# ESP_LoRa_Scale_V1_60.net
KiCad netlist of a schematic drawn in EAGLE
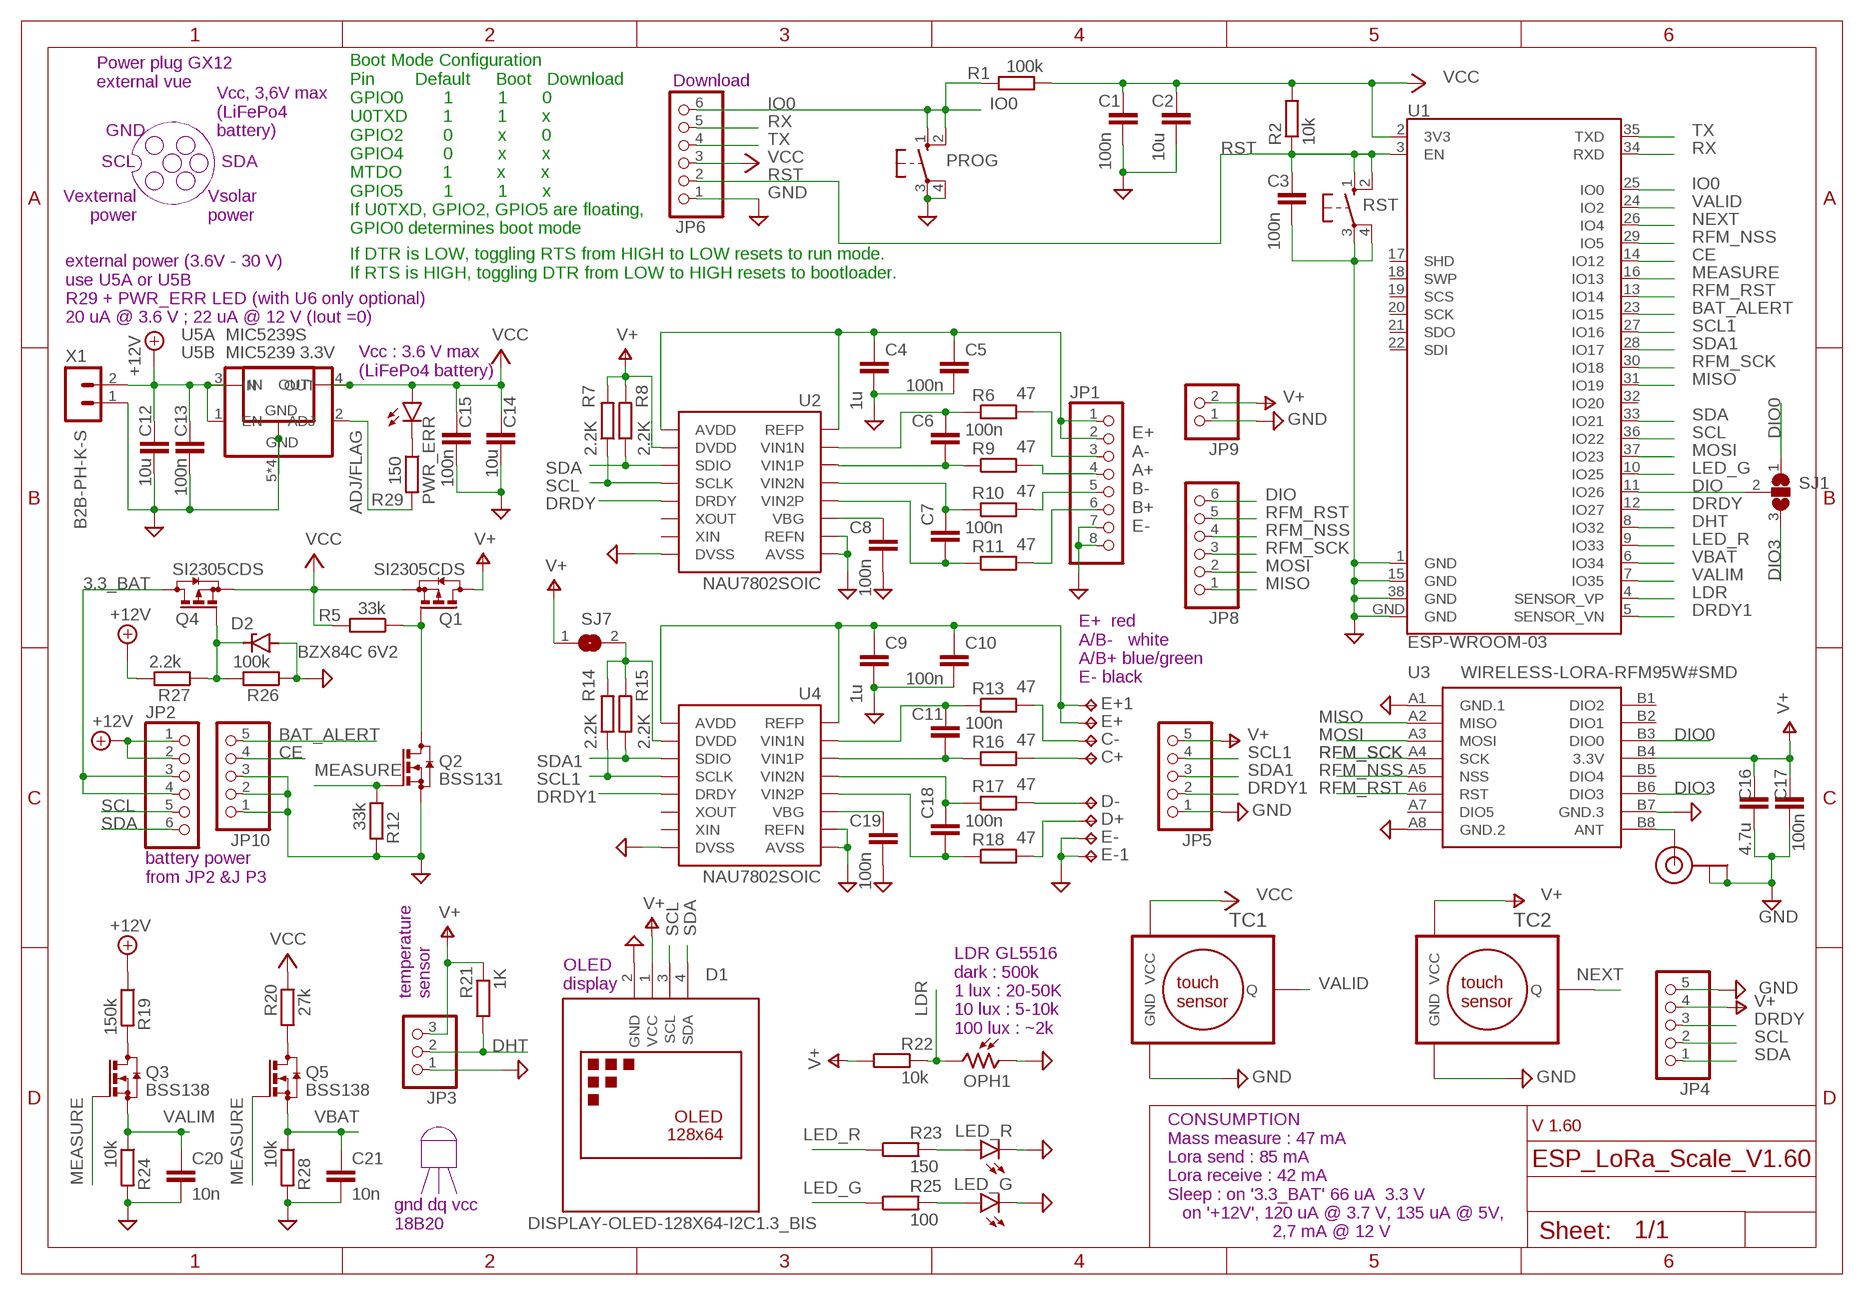
[diagram p0: schematic, sheet 1]

(export (version "E")
  (design (tool "Eeschema 10.0.6"))
  (components
    (comp (ref "C+")
      (value "TPTP17SQ")
      (footprint "eagle-import:TP17SQ")
      (libsource (lib "eagle-import") (part "TPTP17SQ"))
    )
    (comp (ref "C-")
      (value "TPTP17SQ")
      (footprint "eagle-import:TP17SQ")
      (libsource (lib "eagle-import") (part "TPTP17SQ"))
    )
    (comp (ref "C1")
      (value "100n")
      (footprint "eagle-import:C1206")
      (libsource (lib "eagle-import") (part "CC1206"))
    )
    (comp (ref "C2")
      (value "10u")
      (footprint "eagle-import:C1210")
      (libsource (lib "eagle-import") (part "CC1210"))
    )
    (comp (ref "C3")
      (value "100n")
      (footprint "eagle-import:C1206")
      (libsource (lib "eagle-import") (part "CC1206"))
    )
    (comp (ref "C4")
      (value "1u")
      (footprint "eagle-import:C1210")
      (libsource (lib "eagle-import") (part "CC1210"))
    )
    (comp (ref "C5")
      (value "100n")
      (footprint "eagle-import:C1206")
      (libsource (lib "eagle-import") (part "CC1206"))
    )
    (comp (ref "C6")
      (value "100n")
      (footprint "eagle-import:C1206")
      (libsource (lib "eagle-import") (part "CC1206"))
    )
    (comp (ref "C7")
      (value "100n")
      (footprint "eagle-import:C1206")
      (libsource (lib "eagle-import") (part "CC1206"))
    )
    (comp (ref "C8")
      (value "100n")
      (footprint "eagle-import:C1206")
      (libsource (lib "eagle-import") (part "CC1206"))
    )
    (comp (ref "C9")
      (value "1u")
      (footprint "eagle-import:C1210")
      (libsource (lib "eagle-import") (part "CC1210"))
    )
    (comp (ref "C10")
      (value "100n")
      (footprint "eagle-import:C1206")
      (libsource (lib "eagle-import") (part "CC1206"))
    )
    (comp (ref "C11")
      (value "100n")
      (footprint "eagle-import:C1206")
      (libsource (lib "eagle-import") (part "CC1206"))
    )
    (comp (ref "C12")
      (value "10u")
      (footprint "eagle-import:C1210")
      (libsource (lib "eagle-import") (part "CC1210"))
    )
    (comp (ref "C13")
      (value "100n")
      (footprint "eagle-import:C1206")
      (libsource (lib "eagle-import") (part "CC1206"))
    )
    (comp (ref "C14")
      (value "10u")
      (footprint "eagle-import:C1210")
      (libsource (lib "eagle-import") (part "CC1210"))
    )
    (comp (ref "C15")
      (value "100n")
      (footprint "eagle-import:C1206")
      (libsource (lib "eagle-import") (part "CC1206"))
    )
    (comp (ref "C16")
      (value "4.7u")
      (footprint "eagle-import:C1210")
      (libsource (lib "eagle-import") (part "CC1210"))
    )
    (comp (ref "C17")
      (value "100n")
      (footprint "eagle-import:C1206")
      (libsource (lib "eagle-import") (part "CC1206"))
    )
    (comp (ref "C18")
      (value "100n")
      (footprint "eagle-import:C1206")
      (libsource (lib "eagle-import") (part "CC1206"))
    )
    (comp (ref "C19")
      (value "100n")
      (footprint "eagle-import:C1206")
      (libsource (lib "eagle-import") (part "CC1206"))
    )
    (comp (ref "C20")
      (value "10n")
      (footprint "eagle-import:C1206")
      (libsource (lib "eagle-import") (part "CC1206"))
    )
    (comp (ref "C21")
      (value "10n")
      (footprint "eagle-import:C1206")
      (libsource (lib "eagle-import") (part "CC1206"))
    )
    (comp (ref "D+")
      (value "TPTP17SQ")
      (footprint "eagle-import:TP17SQ")
      (libsource (lib "eagle-import") (part "TPTP17SQ"))
    )
    (comp (ref "D-")
      (value "TPTP17SQ")
      (footprint "eagle-import:TP17SQ")
      (libsource (lib "eagle-import") (part "TPTP17SQ"))
    )
    (comp (ref "D1")
      (value "DISPLAY-OLED-128X64-I2C1.3_BIS")
      (footprint "eagle-import:DISPLAY-OLED-128X64-1.3-I2C_BIS")
      (libsource (lib "eagle-import") (part "DISPLAY-OLED-128X64-I2C1.3_BIS"))
    )
    (comp (ref "D2")
      (value "BZX84C 6V2")
      (footprint "eagle-import:TO236")
      (libsource (lib "eagle-import") (part "BZX84CSMD"))
    )
    (comp (ref "E+")
      (value "TPTP17SQ")
      (footprint "eagle-import:TP17SQ")
      (libsource (lib "eagle-import") (part "TPTP17SQ"))
    )
    (comp (ref "E+1")
      (value "TPTP17SQ")
      (footprint "eagle-import:TP17SQ")
      (libsource (lib "eagle-import") (part "TPTP17SQ"))
    )
    (comp (ref "E-")
      (value "TPTP17SQ")
      (footprint "eagle-import:TP17SQ")
      (libsource (lib "eagle-import") (part "TPTP17SQ"))
    )
    (comp (ref "E-1")
      (value "TPTP17SQ")
      (footprint "eagle-import:TP17SQ")
      (libsource (lib "eagle-import") (part "TPTP17SQ"))
    )
    (comp (ref "J1")
      (value "U.FL")
      (footprint "eagle-import:U.FL")
      (libsource (lib "eagle-import") (part "U.FL"))
    )
    (comp (ref "JP1")
      (value "PINHD-1X8")
      (footprint "eagle-import:1X08")
      (libsource (lib "eagle-import") (part "PINHD-1X8"))
    )
    (comp (ref "JP2")
      (value "PINHD-1X6")
      (footprint "eagle-import:1X06")
      (libsource (lib "eagle-import") (part "PINHD-1X6"))
    )
    (comp (ref "JP3")
      (value "PINHD-1X3")
      (footprint "eagle-import:1X03")
      (libsource (lib "eagle-import") (part "PINHD-1X3"))
    )
    (comp (ref "JP4")
      (value "PINHD-1X5")
      (footprint "eagle-import:1X05")
      (libsource (lib "eagle-import") (part "PINHD-1X5"))
    )
    (comp (ref "JP5")
      (value "PINHD-1X5")
      (footprint "eagle-import:1X05")
      (libsource (lib "eagle-import") (part "PINHD-1X5"))
    )
    (comp (ref "JP6")
      (value "PINHD-1X6")
      (footprint "eagle-import:1X06")
      (libsource (lib "eagle-import") (part "PINHD-1X6"))
    )
    (comp (ref "JP8")
      (value "PINHD-1X6")
      (footprint "eagle-import:1X06")
      (libsource (lib "eagle-import") (part "PINHD-1X6"))
    )
    (comp (ref "JP9")
      (value "PINHD-1X2")
      (footprint "eagle-import:1X02")
      (libsource (lib "eagle-import") (part "PINHD-1X2"))
    )
    (comp (ref "JP10")
      (value "PINHD-1X5")
      (footprint "eagle-import:1X05")
      (libsource (lib "eagle-import") (part "PINHD-1X5"))
    )
    (comp (ref "LED_G")
      (value "LEDSMT1206")
      (footprint "eagle-import:1206")
      (libsource (lib "eagle-import") (part "LEDSMT1206"))
    )
    (comp (ref "LED_R")
      (value "LEDSMT1206")
      (footprint "eagle-import:1206")
      (libsource (lib "eagle-import") (part "LEDSMT1206"))
    )
    (comp (ref "OPH1")
      (value "VT93N2")
      (footprint "eagle-import:VT900")
      (libsource (lib "eagle-import") (part "VT93N2"))
    )
    (comp (ref "PROG")
      (value "10-XX")
      (footprint "eagle-import:B3F-10XX")
      (fields (field (name "MPN") "B3F-1000"))
      (libsource (lib "eagle-import") (part "10-XX"))
    )
    (comp (ref "PWR_ERR")
      (value "LEDSMT1206")
      (footprint "eagle-import:1206")
      (libsource (lib "eagle-import") (part "LEDSMT1206"))
    )
    (comp (ref "Q1")
      (value "SI2305CDS")
      (footprint "eagle-import:SOT23")
      (libsource (lib "eagle-import") (part "SI2305CDS"))
    )
    (comp (ref "Q2")
      (value "BSS131")
      (footprint "eagle-import:SOT23")
      (libsource (lib "eagle-import") (part "BSS131"))
    )
    (comp (ref "Q3")
      (value "BSS138")
      (footprint "eagle-import:SOT23")
      (libsource (lib "eagle-import") (part "BSS138"))
    )
    (comp (ref "Q4")
      (value "SI2305CDS")
      (footprint "eagle-import:SOT23")
      (libsource (lib "eagle-import") (part "SI2305CDS"))
    )
    (comp (ref "Q5")
      (value "BSS138")
      (footprint "eagle-import:SOT23")
      (libsource (lib "eagle-import") (part "BSS138"))
    )
    (comp (ref "R1")
      (value "100k")
      (footprint "eagle-import:R1206")
      (libsource (lib "eagle-import") (part "RR1206"))
    )
    (comp (ref "R2")
      (value "10k")
      (footprint "eagle-import:R1206")
      (libsource (lib "eagle-import") (part "RR1206"))
    )
    (comp (ref "R5")
      (value "33k")
      (footprint "eagle-import:R1206")
      (libsource (lib "eagle-import") (part "RR1206"))
    )
    (comp (ref "R6")
      (value "47")
      (footprint "eagle-import:R1206")
      (libsource (lib "eagle-import") (part "RR1206"))
    )
    (comp (ref "R7")
      (value "2.2K")
      (footprint "eagle-import:R1206")
      (libsource (lib "eagle-import") (part "RR1206"))
    )
    (comp (ref "R8")
      (value "2.2K")
      (footprint "eagle-import:R1206")
      (libsource (lib "eagle-import") (part "RR1206"))
    )
    (comp (ref "R9")
      (value "47")
      (footprint "eagle-import:R1206")
      (libsource (lib "eagle-import") (part "RR1206"))
    )
    (comp (ref "R10")
      (value "47")
      (footprint "eagle-import:R1206")
      (libsource (lib "eagle-import") (part "RR1206"))
    )
    (comp (ref "R11")
      (value "47")
      (footprint "eagle-import:R1206")
      (libsource (lib "eagle-import") (part "RR1206"))
    )
    (comp (ref "R12")
      (value "33k")
      (footprint "eagle-import:R1206")
      (libsource (lib "eagle-import") (part "RR1206"))
    )
    (comp (ref "R13")
      (value "47")
      (footprint "eagle-import:R1206")
      (libsource (lib "eagle-import") (part "RR1206"))
    )
    (comp (ref "R14")
      (value "2.2K")
      (footprint "eagle-import:R1206")
      (libsource (lib "eagle-import") (part "RR1206"))
    )
    (comp (ref "R15")
      (value "2.2K")
      (footprint "eagle-import:R1206")
      (libsource (lib "eagle-import") (part "RR1206"))
    )
    (comp (ref "R16")
      (value "47")
      (footprint "eagle-import:R1206")
      (libsource (lib "eagle-import") (part "RR1206"))
    )
    (comp (ref "R17")
      (value "47")
      (footprint "eagle-import:R1206")
      (libsource (lib "eagle-import") (part "RR1206"))
    )
    (comp (ref "R18")
      (value "47")
      (footprint "eagle-import:R1206")
      (libsource (lib "eagle-import") (part "RR1206"))
    )
    (comp (ref "R19")
      (value "150k")
      (footprint "eagle-import:R1206")
      (libsource (lib "eagle-import") (part "RR1206"))
    )
    (comp (ref "R20")
      (value "27k")
      (footprint "eagle-import:R1206")
      (libsource (lib "eagle-import") (part "RR1206"))
    )
    (comp (ref "R21")
      (value "1K")
      (footprint "eagle-import:R1206")
      (libsource (lib "eagle-import") (part "RR1206"))
    )
    (comp (ref "R22")
      (value "10k")
      (footprint "eagle-import:R1206")
      (libsource (lib "eagle-import") (part "RR1206"))
    )
    (comp (ref "R23")
      (value "150")
      (footprint "eagle-import:R1206")
      (libsource (lib "eagle-import") (part "RR1206"))
    )
    (comp (ref "R24")
      (value "10k")
      (footprint "eagle-import:R1206")
      (libsource (lib "eagle-import") (part "RR1206"))
    )
    (comp (ref "R25")
      (value "100")
      (footprint "eagle-import:R1206")
      (libsource (lib "eagle-import") (part "RR1206"))
    )
    (comp (ref "R26")
      (value "100k")
      (footprint "eagle-import:R1206")
      (libsource (lib "eagle-import") (part "RR1206"))
    )
    (comp (ref "R27")
      (value "2.2k")
      (footprint "eagle-import:R1206")
      (libsource (lib "eagle-import") (part "RR1206"))
    )
    (comp (ref "R28")
      (value "10k")
      (footprint "eagle-import:R1206")
      (libsource (lib "eagle-import") (part "RR1206"))
    )
    (comp (ref "R29")
      (value "150")
      (footprint "eagle-import:R1206")
      (libsource (lib "eagle-import") (part "RR1206"))
    )
    (comp (ref "RST")
      (value "10-XX")
      (footprint "eagle-import:B3F-10XX")
      (fields (field (name "MPN") "B3F-1000"))
      (libsource (lib "eagle-import") (part "10-XX"))
    )
    (comp (ref "SJ1")
      (value "SJ2W")
      (footprint "eagle-import:SJ_2")
      (libsource (lib "eagle-import") (part "SJ2W"))
    )
    (comp (ref "SJ7") (value "SJ") (footprint "eagle-import:SJ") (libsource (lib "eagle-import") (part "SJ")))
    (comp (ref "TC1")
      (value "TTP223R_H")
      (footprint "eagle-import:TTP233RED_H")
      (libsource (lib "eagle-import") (part "TTP223R_H"))
    )
    (comp (ref "TC2")
      (value "TTP223R_H")
      (footprint "eagle-import:TTP233RED_H")
      (libsource (lib "eagle-import") (part "TTP223R_H"))
    )
    (comp (ref "U1")
      (value "ESP-WROOM-03")
      (footprint "eagle-import:ESP-WROOM-03")
      (libsource (lib "eagle-import") (part "ESP-WROOM-03"))
    )
    (comp (ref "U2")
      (value "NAU7802SOIC")
      (footprint "eagle-import:SO16")
      (libsource (lib "eagle-import") (part "NAU7802SOIC"))
    )
    (comp (ref "U3")
      (value "WIRELESS-LORA-RFM95W#SMD")
      (footprint "eagle-import:WIRELESS-LORA-RFM95W#SMD")
      (libsource (lib "eagle-import") (part "WIRELESS-LORA-RFM95W#SMD"))
    )
    (comp (ref "U4")
      (value "NAU7802SOIC")
      (footprint "eagle-import:SO16")
      (libsource (lib "eagle-import") (part "NAU7802SOIC"))
    )
    (comp (ref "U5A")
      (value "MIC5239 3.3V")
      (footprint "eagle-import:MSOP08")
      (libsource (lib "eagle-import") (part "MIC5239-ADJMM"))
    )
    (comp (ref "U5B")
      (value "MIC5239S")
      (footprint "eagle-import:SOT223")
      (libsource (lib "eagle-import") (part "MIC5239S"))
    )
    (comp (ref "X1")
      (value "B2B-PH-K-S")
      (footprint "eagle-import:B2B-PH-K-S")
      (libsource (lib "eagle-import") (part "B2B-PH-K-S"))
    )
  )
  (nets
    (net (code "1") (name "+12V") (class "Default")
      (node (ref "C12") (pin "1") (pinfunction "1_1") (pintype "passive"))
      (node (ref "C13") (pin "1") (pinfunction "1_1") (pintype "passive"))
      (node (ref "JP2") (pin "1") (pinfunction "1_1") (pintype "passive"))
      (node (ref "JP2") (pin "2") (pinfunction "2_2") (pintype "passive"))
      (node (ref "R19") (pin "1") (pinfunction "1_1") (pintype "passive"))
      (node (ref "R27") (pin "2") (pinfunction "2_2") (pintype "passive"))
      (node (ref "U5A") (pin "1") (pinfunction "EN_1") (pintype "input"))
      (node (ref "U5A") (pin "3") (pinfunction "IN_3") (pintype "input"))
      (node (ref "U5B") (pin "1") (pinfunction "IN_1") (pintype "input"))
      (node (ref "X1") (pin "2") (pinfunction "2_2") (pintype "passive"))
    )
    (net (code "2") (name "/3.3_BAT") (class "Default")
      (node (ref "JP2") (pin "3") (pinfunction "3_3") (pintype "passive"))
      (node (ref "JP2") (pin "4") (pinfunction "4_4") (pintype "passive"))
      (node (ref "Q4") (pin "3") (pinfunction "D_3") (pintype "passive"))
    )
    (net (code "3") (name "/ADJ{slash}FLAG") (class "Default")
      (node (ref "R29") (pin "2") (pinfunction "2_2") (pintype "passive"))
      (node (ref "U5A") (pin "2") (pinfunction "ADJ_2") (pintype "passive"))
    )
    (net (code "4") (name "/BAT_ALERT") (class "Default")
      (node (ref "JP10") (pin "5") (pinfunction "5_5") (pintype "passive"))
      (node (ref "U1") (pin "23") (pinfunction "IO15_23") (pintype "bidirectional"))
    )
    (net (code "5") (name "/CE") (class "Default")
      (node (ref "JP10") (pin "4") (pinfunction "4_4") (pintype "passive"))
      (node (ref "U1") (pin "14") (pinfunction "IO12_14") (pintype "bidirectional"))
    )
    (net (code "6") (name "/DHT") (class "Default")
      (node (ref "JP3") (pin "2") (pinfunction "2_2") (pintype "passive"))
      (node (ref "R21") (pin "1") (pinfunction "1_1") (pintype "passive"))
      (node (ref "U1") (pin "8") (pinfunction "IO32_8") (pintype "bidirectional"))
    )
    (net (code "7") (name "/DIO") (class "Default")
      (node (ref "JP8") (pin "6") (pinfunction "6_6") (pintype "passive"))
      (node (ref "SJ1") (pin "2") (pinfunction "2_2") (pintype "passive"))
      (node (ref "U1") (pin "11") (pinfunction "IO26_11") (pintype "bidirectional"))
    )
    (net (code "8") (name "/DIO0") (class "Default")
      (node (ref "SJ1") (pin "1") (pinfunction "1_1") (pintype "passive"))
      (node (ref "U3") (pin "B3") (pinfunction "DIO0_B3") (pintype "bidirectional"))
    )
    (net (code "9") (name "/DIO3") (class "Default")
      (node (ref "SJ1") (pin "3") (pinfunction "3_3") (pintype "passive"))
      (node (ref "U3") (pin "B6") (pinfunction "DIO3_B6") (pintype "bidirectional"))
    )
    (net (code "10") (name "/DRDY") (class "Default")
      (node (ref "JP4") (pin "3") (pinfunction "3_3") (pintype "passive"))
      (node (ref "U1") (pin "12") (pinfunction "IO27_12") (pintype "bidirectional"))
      (node (ref "U2") (pin "12") (pinfunction "DRDY_12") (pintype "bidirectional"))
    )
    (net (code "11") (name "/DRDY1") (class "Default")
      (node (ref "JP5") (pin "2") (pinfunction "2_2") (pintype "passive"))
      (node (ref "U1") (pin "5") (pinfunction "SENSOR_VN_5") (pintype "bidirectional"))
      (node (ref "U4") (pin "12") (pinfunction "DRDY_12") (pintype "bidirectional"))
    )
    (net (code "12") (name "/IO0") (class "Default")
      (node (ref "JP6") (pin "6") (pinfunction "6_6") (pintype "passive"))
      (node (ref "PROG") (pin "1") (pinfunction "S_1") (pintype "passive"))
      (node (ref "PROG") (pin "2") (pinfunction "S1_2") (pintype "passive"))
      (node (ref "R1") (pin "2") (pinfunction "2_2") (pintype "passive"))
      (node (ref "U1") (pin "25") (pinfunction "IO0_25") (pintype "bidirectional"))
    )
    (net (code "13") (name "/LDR") (class "Default")
      (node (ref "OPH1") (pin "2") (pinfunction "2_2") (pintype "passive"))
      (node (ref "R22") (pin "2") (pinfunction "2_2") (pintype "passive"))
      (node (ref "U1") (pin "4") (pinfunction "SENSOR_VP_4") (pintype "bidirectional"))
    )
    (net (code "14") (name "/LED_G") (class "Default")
      (node (ref "R25") (pin "1") (pinfunction "1_1") (pintype "passive"))
      (node (ref "U1") (pin "10") (pinfunction "IO25_10") (pintype "bidirectional"))
    )
    (net (code "15") (name "/LED_R") (class "Default")
      (node (ref "R23") (pin "1") (pinfunction "1_1") (pintype "passive"))
      (node (ref "U1") (pin "9") (pinfunction "IO33_9") (pintype "bidirectional"))
    )
    (net (code "16") (name "/MEASURE") (class "Default")
      (node (ref "Q2") (pin "1") (pinfunction "G_1") (pintype "passive"))
      (node (ref "Q3") (pin "1") (pinfunction "G_1") (pintype "passive"))
      (node (ref "Q5") (pin "1") (pinfunction "G_1") (pintype "passive"))
      (node (ref "R12") (pin "1") (pinfunction "1_1") (pintype "passive"))
      (node (ref "U1") (pin "16") (pinfunction "IO13_16") (pintype "bidirectional"))
    )
    (net (code "17") (name "/MISO") (class "Default")
      (node (ref "JP8") (pin "1") (pinfunction "1_1") (pintype "passive"))
      (node (ref "U1") (pin "31") (pinfunction "IO19_31") (pintype "bidirectional"))
      (node (ref "U3") (pin "A2") (pinfunction "MISO_A2") (pintype "bidirectional"))
    )
    (net (code "18") (name "/MOSI") (class "Default")
      (node (ref "JP8") (pin "2") (pinfunction "2_2") (pintype "passive"))
      (node (ref "U1") (pin "37") (pinfunction "IO23_37") (pintype "bidirectional"))
      (node (ref "U3") (pin "A3") (pinfunction "MOSI_A3") (pintype "bidirectional"))
    )
    (net (code "19") (name "/NEXT") (class "Default")
      (node (ref "TC2") (pin "P$2") (pinfunction "Q_P$2") (pintype "power_in"))
      (node (ref "U1") (pin "26") (pinfunction "IO4_26") (pintype "bidirectional"))
    )
    (net (code "20") (name "/RFM_NSS") (class "Default")
      (node (ref "JP8") (pin "4") (pinfunction "4_4") (pintype "passive"))
      (node (ref "U1") (pin "29") (pinfunction "IO5_29") (pintype "bidirectional"))
      (node (ref "U3") (pin "A5") (pinfunction "NSS_A5") (pintype "bidirectional"))
    )
    (net (code "21") (name "/RFM_RST") (class "Default")
      (node (ref "JP8") (pin "5") (pinfunction "5_5") (pintype "passive"))
      (node (ref "U1") (pin "13") (pinfunction "IO14_13") (pintype "bidirectional"))
      (node (ref "U3") (pin "A6") (pinfunction "RST_A6") (pintype "bidirectional"))
    )
    (net (code "22") (name "/RFM_SCK") (class "Default")
      (node (ref "JP8") (pin "3") (pinfunction "3_3") (pintype "passive"))
      (node (ref "U1") (pin "30") (pinfunction "IO18_30") (pintype "bidirectional"))
      (node (ref "U3") (pin "A4") (pinfunction "SCK_A4") (pintype "bidirectional"))
    )
    (net (code "23") (name "/RST") (class "Default")
      (node (ref "C3") (pin "1") (pinfunction "1_1") (pintype "passive"))
      (node (ref "JP6") (pin "2") (pinfunction "2_2") (pintype "passive"))
      (node (ref "R2") (pin "1") (pinfunction "1_1") (pintype "passive"))
      (node (ref "RST") (pin "1") (pinfunction "S_1") (pintype "passive"))
      (node (ref "RST") (pin "2") (pinfunction "S1_2") (pintype "passive"))
      (node (ref "U1") (pin "3") (pinfunction "EN_3") (pintype "bidirectional"))
    )
    (net (code "24") (name "/RX") (class "Default")
      (node (ref "JP6") (pin "5") (pinfunction "5_5") (pintype "passive"))
      (node (ref "U1") (pin "34") (pinfunction "RXD_34") (pintype "bidirectional"))
    )
    (net (code "25") (name "/SCL") (class "Default")
      (node (ref "D1") (pin "3") (pinfunction "SCL_3") (pintype "bidirectional"))
      (node (ref "JP2") (pin "5") (pinfunction "5_5") (pintype "passive"))
      (node (ref "JP4") (pin "2") (pinfunction "2_2") (pintype "passive"))
      (node (ref "R7") (pin "1") (pinfunction "1_1") (pintype "passive"))
      (node (ref "U1") (pin "36") (pinfunction "IO22_36") (pintype "bidirectional"))
      (node (ref "U2") (pin "13") (pinfunction "SCLK_13") (pintype "bidirectional"))
    )
    (net (code "26") (name "/SCL1") (class "Default")
      (node (ref "JP5") (pin "4") (pinfunction "4_4") (pintype "passive"))
      (node (ref "R14") (pin "1") (pinfunction "1_1") (pintype "passive"))
      (node (ref "U1") (pin "27") (pinfunction "IO16_27") (pintype "bidirectional"))
      (node (ref "U4") (pin "13") (pinfunction "SCLK_13") (pintype "bidirectional"))
    )
    (net (code "27") (name "/SDA") (class "Default")
      (node (ref "D1") (pin "4") (pinfunction "SDA_4") (pintype "bidirectional"))
      (node (ref "JP2") (pin "6") (pinfunction "6_6") (pintype "passive"))
      (node (ref "JP4") (pin "1") (pinfunction "1_1") (pintype "passive"))
      (node (ref "R8") (pin "1") (pinfunction "1_1") (pintype "passive"))
      (node (ref "U1") (pin "33") (pinfunction "IO21_33") (pintype "bidirectional"))
      (node (ref "U2") (pin "14") (pinfunction "SDIO_14") (pintype "bidirectional"))
    )
    (net (code "28") (name "/SDA1") (class "Default")
      (node (ref "JP5") (pin "3") (pinfunction "3_3") (pintype "passive"))
      (node (ref "R15") (pin "1") (pinfunction "1_1") (pintype "passive"))
      (node (ref "U1") (pin "28") (pinfunction "IO17_28") (pintype "bidirectional"))
      (node (ref "U4") (pin "14") (pinfunction "SDIO_14") (pintype "bidirectional"))
    )
    (net (code "29") (name "/TX") (class "Default")
      (node (ref "JP6") (pin "4") (pinfunction "4_4") (pintype "passive"))
      (node (ref "U1") (pin "35") (pinfunction "TXD_35") (pintype "bidirectional"))
    )
    (net (code "30") (name "/VALID") (class "Default")
      (node (ref "TC1") (pin "P$2") (pinfunction "Q_P$2") (pintype "power_in"))
      (node (ref "U1") (pin "24") (pinfunction "IO2_24") (pintype "bidirectional"))
    )
    (net (code "31") (name "/VALIM") (class "Default")
      (node (ref "C20") (pin "1") (pinfunction "1_1") (pintype "passive"))
      (node (ref "Q3") (pin "2") (pinfunction "S_2") (pintype "passive"))
      (node (ref "R24") (pin "1") (pinfunction "1_1") (pintype "passive"))
      (node (ref "U1") (pin "7") (pinfunction "IO35_7") (pintype "bidirectional"))
    )
    (net (code "32") (name "/VBAT") (class "Default")
      (node (ref "C21") (pin "1") (pinfunction "1_1") (pintype "passive"))
      (node (ref "Q5") (pin "2") (pinfunction "S_2") (pintype "passive"))
      (node (ref "R28") (pin "1") (pinfunction "1_1") (pintype "passive"))
      (node (ref "U1") (pin "6") (pinfunction "IO34_6") (pintype "bidirectional"))
    )
    (net (code "33") (name "GND") (class "Default")
      (node (ref "C1") (pin "2") (pinfunction "2_2") (pintype "passive"))
      (node (ref "C10") (pin "2") (pinfunction "2_2") (pintype "passive"))
      (node (ref "C12") (pin "2") (pinfunction "2_2") (pintype "passive"))
      (node (ref "C13") (pin "2") (pinfunction "2_2") (pintype "passive"))
      (node (ref "C14") (pin "2") (pinfunction "2_2") (pintype "passive"))
      (node (ref "C15") (pin "2") (pinfunction "2_2") (pintype "passive"))
      (node (ref "C16") (pin "2") (pinfunction "2_2") (pintype "passive"))
      (node (ref "C17") (pin "2") (pinfunction "2_2") (pintype "passive"))
      (node (ref "C19") (pin "2") (pinfunction "2_2") (pintype "passive"))
      (node (ref "C2") (pin "2") (pinfunction "2_2") (pintype "passive"))
      (node (ref "C20") (pin "2") (pinfunction "2_2") (pintype "passive"))
      (node (ref "C21") (pin "2") (pinfunction "2_2") (pintype "passive"))
      (node (ref "C3") (pin "2") (pinfunction "2_2") (pintype "passive"))
      (node (ref "C4") (pin "2") (pinfunction "2_2") (pintype "passive"))
      (node (ref "C5") (pin "2") (pinfunction "2_2") (pintype "passive"))
      (node (ref "C8") (pin "2") (pinfunction "2_2") (pintype "passive"))
      (node (ref "C9") (pin "2") (pinfunction "2_2") (pintype "passive"))
      (node (ref "D1") (pin "2") (pinfunction "GND_2") (pintype "power_in"))
      (node (ref "D2") (pin "A") (pinfunction "A_A") (pintype "passive"))
      (node (ref "E-") (pin "TP") (pinfunction "TP_TP") (pintype "input"))
      (node (ref "E-1") (pin "TP") (pinfunction "TP_TP") (pintype "input"))
      (node (ref "J1") (pin "1") (pinfunction "GND_1") (pintype "passive"))
      (node (ref "J1") (pin "2") (pinfunction "GND_2") (pintype "passive"))
      (node (ref "JP1") (pin "7") (pinfunction "7_7") (pintype "passive"))
      (node (ref "JP1") (pin "8") (pinfunction "8_8") (pintype "passive"))
      (node (ref "JP10") (pin "1") (pinfunction "1_1") (pintype "passive"))
      (node (ref "JP10") (pin "2") (pinfunction "2_2") (pintype "passive"))
      (node (ref "JP10") (pin "3") (pinfunction "3_3") (pintype "passive"))
      (node (ref "JP3") (pin "1") (pinfunction "1_1") (pintype "passive"))
      (node (ref "JP4") (pin "5") (pinfunction "5_5") (pintype "passive"))
      (node (ref "JP5") (pin "1") (pinfunction "1_1") (pintype "passive"))
      (node (ref "JP6") (pin "1") (pinfunction "1_1") (pintype "passive"))
      (node (ref "JP9") (pin "1") (pinfunction "1_1") (pintype "passive"))
      (node (ref "LED_G") (pin "C") (pinfunction "C_C") (pintype "passive"))
      (node (ref "LED_R") (pin "C") (pinfunction "C_C") (pintype "passive"))
      (node (ref "OPH1") (pin "1") (pinfunction "1_1") (pintype "passive"))
      (node (ref "PROG") (pin "3") (pinfunction "P_3") (pintype "passive"))
      (node (ref "PROG") (pin "4") (pinfunction "P1_4") (pintype "passive"))
      (node (ref "Q2") (pin "2") (pinfunction "S_2") (pintype "passive"))
      (node (ref "R12") (pin "2") (pinfunction "2_2") (pintype "passive"))
      (node (ref "R24") (pin "2") (pinfunction "2_2") (pintype "passive"))
      (node (ref "R26") (pin "1") (pinfunction "1_1") (pintype "passive"))
      (node (ref "R28") (pin "2") (pinfunction "2_2") (pintype "passive"))
      (node (ref "RST") (pin "3") (pinfunction "P_3") (pintype "passive"))
      (node (ref "RST") (pin "4") (pinfunction "P1_4") (pintype "passive"))
      (node (ref "TC1") (pin "P$3") (pinfunction "GND_P$3") (pintype "power_in"))
      (node (ref "TC2") (pin "P$3") (pinfunction "GND_P$3") (pintype "power_in"))
      (node (ref "U1") (pin "1") (pinfunction "GND_1") (pintype "bidirectional"))
      (node (ref "U1") (pin "15") (pinfunction "GND_15") (pintype "bidirectional"))
      (node (ref "U1") (pin "38") (pinfunction "GND_38") (pintype "bidirectional"))
      (node (ref "U1") (pin "GND") (pinfunction "GND_GND") (pintype "bidirectional"))
      (node (ref "U2") (pin "7") (pinfunction "REFN_7") (pintype "bidirectional"))
      (node (ref "U2") (pin "8") (pinfunction "AVSS_8") (pintype "bidirectional"))
      (node (ref "U2") (pin "9") (pinfunction "DVSS_9") (pintype "bidirectional"))
      (node (ref "U3") (pin "A1") (pinfunction "GND.1_A1") (pintype "power_in"))
      (node (ref "U3") (pin "A8") (pinfunction "GND.2_A8") (pintype "power_in"))
      (node (ref "U3") (pin "B7") (pinfunction "GND.3_B7") (pintype "power_in"))
      (node (ref "U4") (pin "7") (pinfunction "REFN_7") (pintype "bidirectional"))
      (node (ref "U4") (pin "8") (pinfunction "AVSS_8") (pintype "bidirectional"))
      (node (ref "U4") (pin "9") (pinfunction "DVSS_9") (pintype "bidirectional"))
      (node (ref "U5A") (pin "5") (pinfunction "GND_5") (pintype "power_in"))
      (node (ref "U5A") (pin "6") (pinfunction "GND_6") (pintype "power_in"))
      (node (ref "U5A") (pin "7") (pinfunction "GND_7") (pintype "power_in"))
      (node (ref "U5A") (pin "8") (pinfunction "GND_8") (pintype "power_in"))
      (node (ref "U5B") (pin "2") (pinfunction "GND_2") (pintype "passive"))
      (node (ref "U5B") (pin "4") (pinfunction "GND_4") (pintype "passive"))
      (node (ref "X1") (pin "1") (pinfunction "1_1") (pintype "passive"))
    )
    (net (code "34") (name "Net-(C+-PadTP)") (class "Default")
      (node (ref "C+") (pin "TP") (pinfunction "TP_TP") (pintype "input"))
      (node (ref "R16") (pin "2") (pinfunction "2_2") (pintype "passive"))
    )
    (net (code "35") (name "Net-(C--PadTP)") (class "Default")
      (node (ref "C-") (pin "TP") (pinfunction "TP_TP") (pintype "input"))
      (node (ref "R13") (pin "2") (pinfunction "2_2") (pintype "passive"))
    )
    (net (code "36") (name "Net-(D+-PadTP)") (class "Default")
      (node (ref "D+") (pin "TP") (pinfunction "TP_TP") (pintype "input"))
      (node (ref "R18") (pin "2") (pinfunction "2_2") (pintype "passive"))
    )
    (net (code "37") (name "Net-(D--PadTP)") (class "Default")
      (node (ref "D-") (pin "TP") (pinfunction "TP_TP") (pintype "input"))
      (node (ref "R17") (pin "2") (pinfunction "2_2") (pintype "passive"))
    )
    (net (code "38") (name "Net-(J1-SIGNAL)") (class "Default")
      (node (ref "J1") (pin "3") (pinfunction "SIGNAL_3") (pintype "passive"))
      (node (ref "U3") (pin "B8") (pinfunction "ANT_B8") (pintype "passive"))
    )
    (net (code "39") (name "Net-(JP1-Pad3)") (class "Default")
      (node (ref "JP1") (pin "3") (pinfunction "3_3") (pintype "passive"))
      (node (ref "R6") (pin "2") (pinfunction "2_2") (pintype "passive"))
    )
    (net (code "40") (name "Net-(JP1-Pad4)") (class "Default")
      (node (ref "JP1") (pin "4") (pinfunction "4_4") (pintype "passive"))
      (node (ref "R9") (pin "2") (pinfunction "2_2") (pintype "passive"))
    )
    (net (code "41") (name "Net-(JP1-Pad5)") (class "Default")
      (node (ref "JP1") (pin "5") (pinfunction "5_5") (pintype "passive"))
      (node (ref "R10") (pin "2") (pinfunction "2_2") (pintype "passive"))
    )
    (net (code "42") (name "Net-(JP1-Pad6)") (class "Default")
      (node (ref "JP1") (pin "6") (pinfunction "6_6") (pintype "passive"))
      (node (ref "R11") (pin "2") (pinfunction "2_2") (pintype "passive"))
    )
    (net (code "43") (name "Net-(LED_G-PadA)") (class "Default")
      (node (ref "LED_G") (pin "A") (pinfunction "A_A") (pintype "passive"))
      (node (ref "R25") (pin "2") (pinfunction "2_2") (pintype "passive"))
    )
    (net (code "44") (name "Net-(LED_R-PadA)") (class "Default")
      (node (ref "LED_R") (pin "A") (pinfunction "A_A") (pintype "passive"))
      (node (ref "R23") (pin "2") (pinfunction "2_2") (pintype "passive"))
    )
    (net (code "45") (name "Net-(PWR_ERR-PadC)") (class "Default")
      (node (ref "PWR_ERR") (pin "C") (pinfunction "C_C") (pintype "passive"))
      (node (ref "R29") (pin "1") (pinfunction "1_1") (pintype "passive"))
    )
    (net (code "46") (name "Net-(Q1-G)") (class "Default")
      (node (ref "Q1") (pin "1") (pinfunction "G_1") (pintype "passive"))
      (node (ref "Q2") (pin "3") (pinfunction "D_3") (pintype "passive"))
      (node (ref "R5") (pin "1") (pinfunction "1_1") (pintype "passive"))
    )
    (net (code "47") (name "Net-(Q3-D)") (class "Default")
      (node (ref "Q3") (pin "3") (pinfunction "D_3") (pintype "passive"))
      (node (ref "R19") (pin "2") (pinfunction "2_2") (pintype "passive"))
    )
    (net (code "48") (name "Net-(Q4-G)") (class "Default")
      (node (ref "D2") (pin "C") (pinfunction "C_C") (pintype "passive"))
      (node (ref "Q4") (pin "1") (pinfunction "G_1") (pintype "passive"))
      (node (ref "R26") (pin "2") (pinfunction "2_2") (pintype "passive"))
      (node (ref "R27") (pin "1") (pinfunction "1_1") (pintype "passive"))
    )
    (net (code "49") (name "Net-(Q5-D)") (class "Default")
      (node (ref "Q5") (pin "3") (pinfunction "D_3") (pintype "passive"))
      (node (ref "R20") (pin "1") (pinfunction "1_1") (pintype "passive"))
    )
    (net (code "50") (name "Net-(U2-AVDD)") (class "Default")
      (node (ref "C4") (pin "1") (pinfunction "1_1") (pintype "passive"))
      (node (ref "C5") (pin "1") (pinfunction "1_1") (pintype "passive"))
      (node (ref "JP1") (pin "1") (pinfunction "1_1") (pintype "passive"))
      (node (ref "JP1") (pin "2") (pinfunction "2_2") (pintype "passive"))
      (node (ref "U2") (pin "1") (pinfunction "REFP_1") (pintype "bidirectional"))
      (node (ref "U2") (pin "16") (pinfunction "AVDD_16") (pintype "bidirectional"))
    )
    (net (code "51") (name "Net-(U2-VBG)") (class "Default")
      (node (ref "C8") (pin "1") (pinfunction "1_1") (pintype "passive"))
      (node (ref "U2") (pin "6") (pinfunction "VBG_6") (pintype "bidirectional"))
    )
    (net (code "52") (name "Net-(U2-VIN1N)") (class "Default")
      (node (ref "C6") (pin "1") (pinfunction "1_1") (pintype "passive"))
      (node (ref "R6") (pin "1") (pinfunction "1_1") (pintype "passive"))
      (node (ref "U2") (pin "2") (pinfunction "VIN1N_2") (pintype "bidirectional"))
    )
    (net (code "53") (name "Net-(U2-VIN1P)") (class "Default")
      (node (ref "C6") (pin "2") (pinfunction "2_2") (pintype "passive"))
      (node (ref "R9") (pin "1") (pinfunction "1_1") (pintype "passive"))
      (node (ref "U2") (pin "3") (pinfunction "VIN1P_3") (pintype "bidirectional"))
    )
    (net (code "54") (name "Net-(U2-VIN2N)") (class "Default")
      (node (ref "C7") (pin "1") (pinfunction "1_1") (pintype "passive"))
      (node (ref "R10") (pin "1") (pinfunction "1_1") (pintype "passive"))
      (node (ref "U2") (pin "4") (pinfunction "VIN2N_4") (pintype "bidirectional"))
    )
    (net (code "55") (name "Net-(U2-VIN2P)") (class "Default")
      (node (ref "C7") (pin "2") (pinfunction "2_2") (pintype "passive"))
      (node (ref "R11") (pin "1") (pinfunction "1_1") (pintype "passive"))
      (node (ref "U2") (pin "5") (pinfunction "VIN2P_5") (pintype "bidirectional"))
    )
    (net (code "56") (name "Net-(U4-AVDD)") (class "Default")
      (node (ref "C10") (pin "1") (pinfunction "1_1") (pintype "passive"))
      (node (ref "C9") (pin "1") (pinfunction "1_1") (pintype "passive"))
      (node (ref "E+") (pin "TP") (pinfunction "TP_TP") (pintype "input"))
      (node (ref "E+1") (pin "TP") (pinfunction "TP_TP") (pintype "input"))
      (node (ref "U4") (pin "1") (pinfunction "REFP_1") (pintype "bidirectional"))
      (node (ref "U4") (pin "16") (pinfunction "AVDD_16") (pintype "bidirectional"))
    )
    (net (code "57") (name "Net-(U4-DVDD)") (class "Default")
      (node (ref "R14") (pin "2") (pinfunction "2_2") (pintype "passive"))
      (node (ref "R15") (pin "2") (pinfunction "2_2") (pintype "passive"))
      (node (ref "SJ7") (pin "2") (pinfunction "2_2") (pintype "passive"))
      (node (ref "U4") (pin "15") (pinfunction "DVDD_15") (pintype "bidirectional"))
    )
    (net (code "58") (name "Net-(U4-VBG)") (class "Default")
      (node (ref "C19") (pin "1") (pinfunction "1_1") (pintype "passive"))
      (node (ref "U4") (pin "6") (pinfunction "VBG_6") (pintype "bidirectional"))
    )
    (net (code "59") (name "Net-(U4-VIN1N)") (class "Default")
      (node (ref "C11") (pin "1") (pinfunction "1_1") (pintype "passive"))
      (node (ref "R13") (pin "1") (pinfunction "1_1") (pintype "passive"))
      (node (ref "U4") (pin "2") (pinfunction "VIN1N_2") (pintype "bidirectional"))
    )
    (net (code "60") (name "Net-(U4-VIN1P)") (class "Default")
      (node (ref "C11") (pin "2") (pinfunction "2_2") (pintype "passive"))
      (node (ref "R16") (pin "1") (pinfunction "1_1") (pintype "passive"))
      (node (ref "U4") (pin "3") (pinfunction "VIN1P_3") (pintype "bidirectional"))
    )
    (net (code "61") (name "Net-(U4-VIN2N)") (class "Default")
      (node (ref "C18") (pin "1") (pinfunction "1_1") (pintype "passive"))
      (node (ref "R17") (pin "1") (pinfunction "1_1") (pintype "passive"))
      (node (ref "U4") (pin "4") (pinfunction "VIN2N_4") (pintype "bidirectional"))
    )
    (net (code "62") (name "Net-(U4-VIN2P)") (class "Default")
      (node (ref "C18") (pin "2") (pinfunction "2_2") (pintype "passive"))
      (node (ref "R18") (pin "1") (pinfunction "1_1") (pintype "passive"))
      (node (ref "U4") (pin "5") (pinfunction "VIN2P_5") (pintype "bidirectional"))
    )
    (net (code "63") (name "V+") (class "Default")
      (node (ref "C16") (pin "1") (pinfunction "1_1") (pintype "passive"))
      (node (ref "C17") (pin "1") (pinfunction "1_1") (pintype "passive"))
      (node (ref "D1") (pin "1") (pinfunction "VCC_1") (pintype "power_in"))
      (node (ref "JP3") (pin "3") (pinfunction "3_3") (pintype "passive"))
      (node (ref "JP4") (pin "4") (pinfunction "4_4") (pintype "passive"))
      (node (ref "JP5") (pin "5") (pinfunction "5_5") (pintype "passive"))
      (node (ref "JP9") (pin "2") (pinfunction "2_2") (pintype "passive"))
      (node (ref "Q1") (pin "3") (pinfunction "D_3") (pintype "passive"))
      (node (ref "R21") (pin "2") (pinfunction "2_2") (pintype "passive"))
      (node (ref "R22") (pin "1") (pinfunction "1_1") (pintype "passive"))
      (node (ref "R7") (pin "2") (pinfunction "2_2") (pintype "passive"))
      (node (ref "R8") (pin "2") (pinfunction "2_2") (pintype "passive"))
      (node (ref "SJ7") (pin "1") (pinfunction "1_1") (pintype "passive"))
      (node (ref "TC2") (pin "P$1") (pinfunction "VCC_P$1") (pintype "power_in"))
      (node (ref "U2") (pin "15") (pinfunction "DVDD_15") (pintype "bidirectional"))
      (node (ref "U3") (pin "B4") (pinfunction "3.3V_B4") (pintype "power_in"))
    )
    (net (code "64") (name "VCC") (class "Default")
      (node (ref "C1") (pin "1") (pinfunction "1_1") (pintype "passive"))
      (node (ref "C14") (pin "1") (pinfunction "1_1") (pintype "passive"))
      (node (ref "C15") (pin "1") (pinfunction "1_1") (pintype "passive"))
      (node (ref "C2") (pin "1") (pinfunction "1_1") (pintype "passive"))
      (node (ref "JP6") (pin "3") (pinfunction "3_3") (pintype "passive"))
      (node (ref "PWR_ERR") (pin "A") (pinfunction "A_A") (pintype "passive"))
      (node (ref "Q1") (pin "2") (pinfunction "S_2") (pintype "passive"))
      (node (ref "Q4") (pin "2") (pinfunction "S_2") (pintype "passive"))
      (node (ref "R1") (pin "1") (pinfunction "1_1") (pintype "passive"))
      (node (ref "R2") (pin "2") (pinfunction "2_2") (pintype "passive"))
      (node (ref "R20") (pin "2") (pinfunction "2_2") (pintype "passive"))
      (node (ref "R5") (pin "2") (pinfunction "2_2") (pintype "passive"))
      (node (ref "TC1") (pin "P$1") (pinfunction "VCC_P$1") (pintype "power_in"))
      (node (ref "U1") (pin "2") (pinfunction "3V3_2") (pintype "bidirectional"))
      (node (ref "U5A") (pin "4") (pinfunction "OUT_4") (pintype "passive"))
      (node (ref "U5B") (pin "3") (pinfunction "OUT_3") (pintype "passive"))
    )
    (net (code "65") (name "unconnected-(U1-IO20-Pad32)") (class "Default")
      (node (ref "U1") (pin "32") (pinfunction "IO20_32") (pintype "bidirectional"))
    )
    (net (code "66") (name "unconnected-(U1-SCK-Pad20)") (class "Default")
      (node (ref "U1") (pin "20") (pinfunction "SCK_20") (pintype "bidirectional"))
    )
    (net (code "67") (name "unconnected-(U1-SCS-Pad19)") (class "Default")
      (node (ref "U1") (pin "19") (pinfunction "SCS_19") (pintype "bidirectional"))
    )
    (net (code "68") (name "unconnected-(U1-SDI-Pad22)") (class "Default")
      (node (ref "U1") (pin "22") (pinfunction "SDI_22") (pintype "bidirectional"))
    )
    (net (code "69") (name "unconnected-(U1-SDO-Pad21)") (class "Default")
      (node (ref "U1") (pin "21") (pinfunction "SDO_21") (pintype "bidirectional"))
    )
    (net (code "70") (name "unconnected-(U1-SHD-Pad17)") (class "Default")
      (node (ref "U1") (pin "17") (pinfunction "SHD_17") (pintype "bidirectional"))
    )
    (net (code "71") (name "unconnected-(U1-SWP-Pad18)") (class "Default")
      (node (ref "U1") (pin "18") (pinfunction "SWP_18") (pintype "bidirectional"))
    )
    (net (code "72") (name "unconnected-(U2-XIN-Pad10)") (class "Default")
      (node (ref "U2") (pin "10") (pinfunction "XIN_10") (pintype "bidirectional"))
    )
    (net (code "73") (name "unconnected-(U2-XOUT-Pad11)") (class "Default")
      (node (ref "U2") (pin "11") (pinfunction "XOUT_11") (pintype "bidirectional"))
    )
    (net (code "74") (name "unconnected-(U3-DIO1-PadB2)") (class "Default")
      (node (ref "U3") (pin "B2") (pinfunction "DIO1_B2") (pintype "bidirectional"))
    )
    (net (code "75") (name "unconnected-(U3-DIO2-PadB1)") (class "Default")
      (node (ref "U3") (pin "B1") (pinfunction "DIO2_B1") (pintype "bidirectional"))
    )
    (net (code "76") (name "unconnected-(U3-DIO4-PadB5)") (class "Default")
      (node (ref "U3") (pin "B5") (pinfunction "DIO4_B5") (pintype "bidirectional"))
    )
    (net (code "77") (name "unconnected-(U3-DIO5-PadA7)") (class "Default")
      (node (ref "U3") (pin "A7") (pinfunction "DIO5_A7") (pintype "bidirectional"))
    )
    (net (code "78") (name "unconnected-(U4-XIN-Pad10)") (class "Default")
      (node (ref "U4") (pin "10") (pinfunction "XIN_10") (pintype "bidirectional"))
    )
    (net (code "79") (name "unconnected-(U4-XOUT-Pad11)") (class "Default")
      (node (ref "U4") (pin "11") (pinfunction "XOUT_11") (pintype "bidirectional"))
    )
  )
)
